# 15_FPGA_misc_banks.net
KiCad netlist of a schematic drawn in Altium Designer
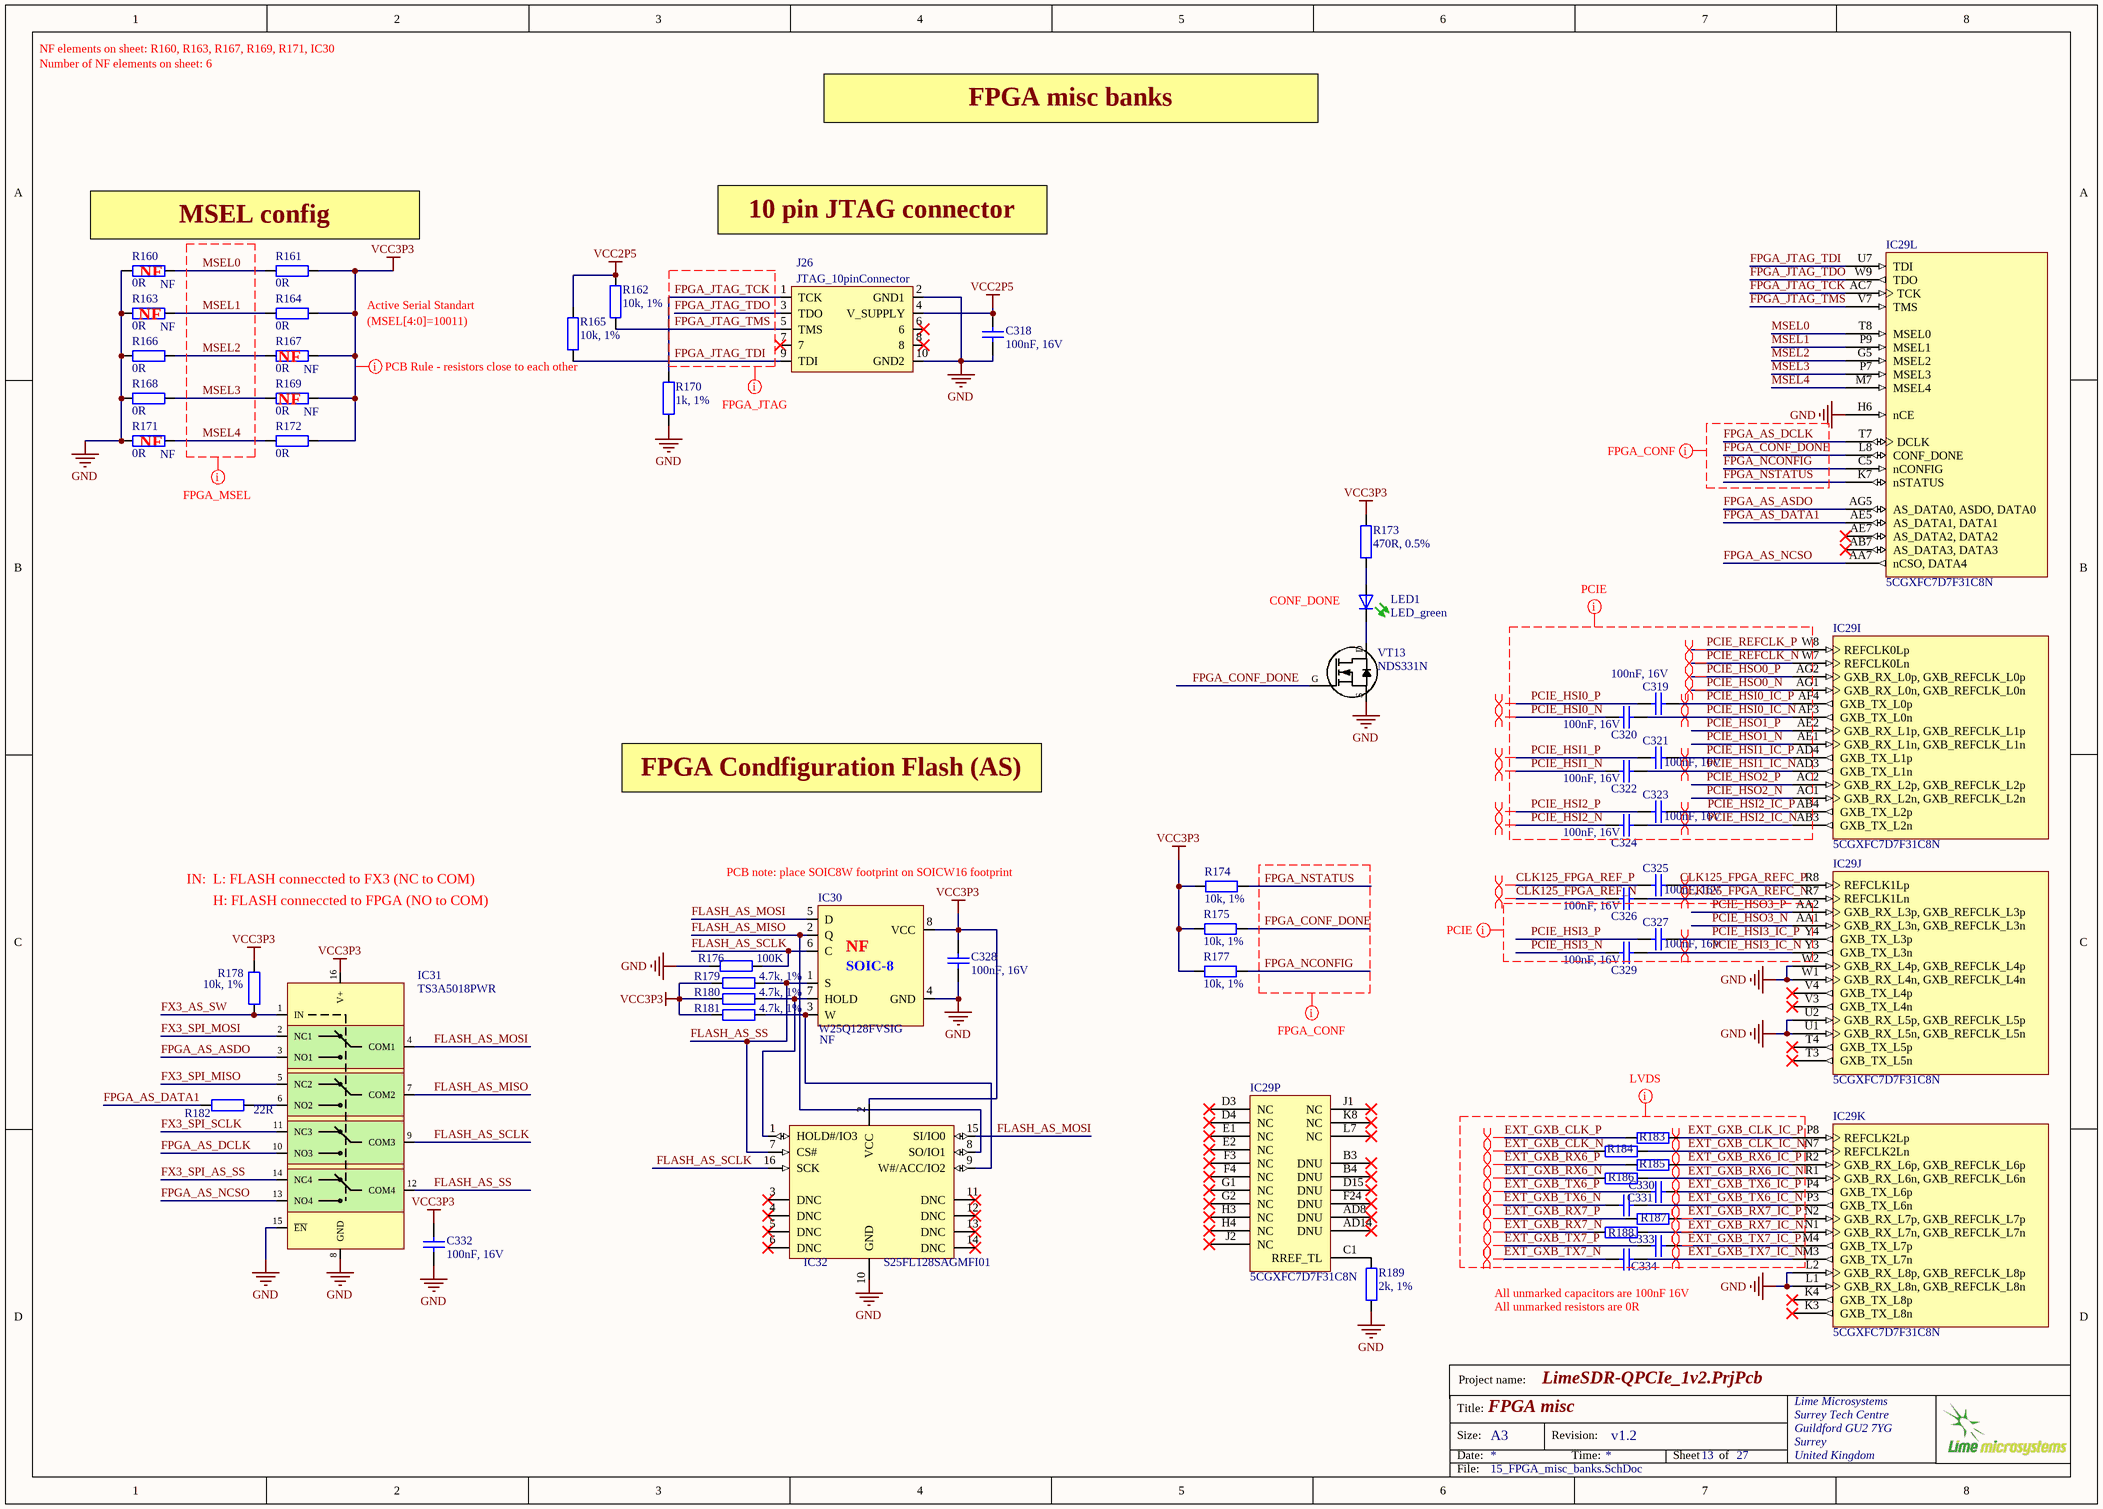
[diagram p0: 15_FPGA_misc_banks.SchDoc]

(export (version "E")
  (design (tool "Eeschema 10.0.6"))
  (components
    (comp (ref "C318")
      (value "100nF, 16V")
      (footprint "CAP0402")
      (fields
        (field (name "TOLERANCE") "10 %")
        (field (name "MANUFACTURER") "Murata Electronics")
        (field (name "MANUFACTURER PART NUMBER") "GRM155R71C104KA88D")
      )
      (libsource (lib "LimeFPGAboard_schLib") (part "Cap_0603"))
    )
    (comp (ref "C319")
      (value "100nF, 16V")
      (footprint "CAP0402")
      (fields
        (field (name "TOLERANCE") "10 %")
        (field (name "MANUFACTURER") "Murata Electronics")
        (field (name "MANUFACTURER PART NUMBER") "GRM155R71C104KA88D")
      )
      (libsource (lib "LimeFPGAboard_schLib") (part "Cap_0603"))
    )
    (comp (ref "C320")
      (value "100nF, 16V")
      (footprint "CAP0402")
      (fields
        (field (name "TOLERANCE") "10 %")
        (field (name "MANUFACTURER") "Murata Electronics")
        (field (name "MANUFACTURER PART NUMBER") "GRM155R71C104KA88D")
      )
      (libsource (lib "LimeFPGAboard_schLib") (part "Cap_0603"))
    )
    (comp (ref "C321")
      (value "100nF, 16V")
      (footprint "CAP0402")
      (fields
        (field (name "TOLERANCE") "10 %")
        (field (name "MANUFACTURER") "Murata Electronics")
        (field (name "MANUFACTURER PART NUMBER") "GRM155R71C104KA88D")
      )
      (libsource (lib "LimeFPGAboard_schLib") (part "Cap_0603"))
    )
    (comp (ref "C322")
      (value "100nF, 16V")
      (footprint "CAP0402")
      (fields
        (field (name "TOLERANCE") "10 %")
        (field (name "MANUFACTURER") "Murata Electronics")
        (field (name "MANUFACTURER PART NUMBER") "GRM155R71C104KA88D")
      )
      (libsource (lib "LimeFPGAboard_schLib") (part "Cap_0603"))
    )
    (comp (ref "C323")
      (value "100nF, 16V")
      (footprint "CAP0402")
      (fields
        (field (name "TOLERANCE") "10 %")
        (field (name "MANUFACTURER") "Murata Electronics")
        (field (name "MANUFACTURER PART NUMBER") "GRM155R71C104KA88D")
      )
      (libsource (lib "LimeFPGAboard_schLib") (part "Cap_0603"))
    )
    (comp (ref "C324")
      (value "100nF, 16V")
      (footprint "CAP0402")
      (fields
        (field (name "TOLERANCE") "10 %")
        (field (name "MANUFACTURER") "Murata Electronics")
        (field (name "MANUFACTURER PART NUMBER") "GRM155R71C104KA88D")
      )
      (libsource (lib "LimeFPGAboard_schLib") (part "Cap_0603"))
    )
    (comp (ref "C325")
      (value "100nF, 16V")
      (footprint "CAP0402")
      (fields
        (field (name "TOLERANCE") "10 %")
        (field (name "MANUFACTURER") "Murata Electronics")
        (field (name "MANUFACTURER PART NUMBER") "GRM155R71C104KA88D")
      )
      (libsource (lib "LimeFPGAboard_schLib") (part "Cap_0603"))
    )
    (comp (ref "C326")
      (value "100nF, 16V")
      (footprint "CAP0402")
      (fields
        (field (name "TOLERANCE") "10 %")
        (field (name "MANUFACTURER") "Murata Electronics")
        (field (name "MANUFACTURER PART NUMBER") "GRM155R71C104KA88D")
      )
      (libsource (lib "LimeFPGAboard_schLib") (part "Cap_0603"))
    )
    (comp (ref "C327")
      (value "100nF, 16V")
      (footprint "CAP0402")
      (fields
        (field (name "TOLERANCE") "10 %")
        (field (name "MANUFACTURER") "Murata Electronics")
        (field (name "MANUFACTURER PART NUMBER") "GRM155R71C104KA88D")
      )
      (libsource (lib "LimeFPGAboard_schLib") (part "Cap_0603"))
    )
    (comp (ref "C328")
      (value "100nF, 16V")
      (footprint "CAP0402")
      (fields
        (field (name "TOLERANCE") "10 %")
        (field (name "MANUFACTURER") "Murata Electronics")
        (field (name "MANUFACTURER PART NUMBER") "GRM155R71C104KA88D")
      )
      (libsource (lib "LimeFPGAboard_schLib") (part "Cap_0603"))
    )
    (comp (ref "C329")
      (value "100nF, 16V")
      (footprint "CAP0402")
      (fields
        (field (name "TOLERANCE") "10 %")
        (field (name "MANUFACTURER") "Murata Electronics")
        (field (name "MANUFACTURER PART NUMBER") "GRM155R71C104KA88D")
      )
      (libsource (lib "LimeFPGAboard_schLib") (part "Cap_0603"))
    )
    (comp (ref "C330")
      (value "100nF, 16V")
      (footprint "CAP0402")
      (fields
        (field (name "TOLERANCE") "10 %")
        (field (name "MANUFACTURER") "Murata Electronics")
        (field (name "MANUFACTURER PART NUMBER") "GRM155R71C104KA88D")
      )
      (libsource (lib "LimeFPGAboard_schLib") (part "Cap_0603"))
    )
    (comp (ref "C331")
      (value "100nF, 16V")
      (footprint "CAP0402")
      (fields
        (field (name "TOLERANCE") "10 %")
        (field (name "MANUFACTURER") "Murata Electronics")
        (field (name "MANUFACTURER PART NUMBER") "GRM155R71C104KA88D")
      )
      (libsource (lib "LimeFPGAboard_schLib") (part "Cap_0603"))
    )
    (comp (ref "C332")
      (value "100nF, 16V")
      (footprint "CAP0402")
      (fields
        (field (name "TOLERANCE") "10 %")
        (field (name "MANUFACTURER") "Murata Electronics")
        (field (name "MANUFACTURER PART NUMBER") "GRM155R71C104KA88D")
      )
      (libsource (lib "LimeFPGAboard_schLib") (part "Cap_0603"))
    )
    (comp (ref "C333")
      (value "100nF, 16V")
      (footprint "CAP0402")
      (fields
        (field (name "TOLERANCE") "10 %")
        (field (name "MANUFACTURER") "Murata Electronics")
        (field (name "MANUFACTURER PART NUMBER") "GRM155R71C104KA88D")
      )
      (libsource (lib "LimeFPGAboard_schLib") (part "Cap_0603"))
    )
    (comp (ref "C334")
      (value "100nF, 16V")
      (footprint "CAP0402")
      (fields
        (field (name "TOLERANCE") "10 %")
        (field (name "MANUFACTURER") "Murata Electronics")
        (field (name "MANUFACTURER PART NUMBER") "GRM155R71C104KA88D")
      )
      (libsource (lib "LimeFPGAboard_schLib") (part "Cap_0603"))
    )
    (comp (ref "IC29")
      (value "5CGXFC7D7F31C8N")
      (footprint "ALTR-FBGA896_A-200")
      (fields (field (name "MANUFACTURER") "Altera"))
      (libsource (lib "LimeMicroAltiumLib_schLib") (part "5CGXFC7D7F31C8N"))
    )
    (comp (ref "IC30")
      (value "W25Q128FVSIG")
      (footprint "S25FL164K_WSO8N")
      (fields (field (name "MANUFACTURER") "Winbond Electronics") (field (name "ASSEMBLY INFO") "NF"))
      (libsource (lib "LimeFPGAboard_schLib") (part "M25P40"))
    )
    (comp (ref "IC31")
      (value "TS3A5018PWR")
      (footprint "TS3A5018PWR")
      (fields (field (name "MANUFACTURER") "Texas Instruments"))
      (libsource (lib "LimeFPGAboard_schLib") (part "TS3A5018PWR"))
    )
    (comp (ref "IC32")
      (value "S25FL128SAGMFI01")
      (footprint "SOIC16_WIDE")
      (fields
        (field (name "MANUFACTURER PART NUMBER") "S25FL128SAGMFI010")
        (field (name "MANUFACTURER") "Spansion")
      )
      (libsource (lib "LimeMicroAltiumLib_schLib") (part "S25FL032P"))
    )
    (comp (ref "J26")
      (value "JTAG_10pinConnector")
      (footprint "HEADER5x2_SM")
      (fields (field (name "MANUFACTURER") "Amphenol FCI"))
      (libsource (lib "LimeFPGAboard_schLib") (part "JTAG_connector_10pin"))
    )
    (comp (ref "LED1")
      (value "LED_green")
      (footprint "LED-0603-GREEN")
      (fields (field (name "MANUFACTURER") "Avago Technologies US Inc."))
      (libsource (lib "LimeFPGAboard_schLib") (part "LED_green"))
    )
    (comp (ref "R160")
      (value "0R")
      (footprint "RES0402")
      (fields (field (name "MANUFACTURER") "Yageo") (field (name "ASSEMBLY INFO") "NF"))
      (libsource (lib "LimeFPGAboard_schLib") (part "Res_0402"))
    )
    (comp (ref "R161")
      (value "0R")
      (footprint "RES0402")
      (fields (field (name "MANUFACTURER") "Yageo"))
      (libsource (lib "LimeFPGAboard_schLib") (part "Res_0402"))
    )
    (comp (ref "R162")
      (value "10k, 1%")
      (footprint "RES0402")
      (fields (field (name "MANUFACTURER") "Yageo") (field (name "TOLERANCE") "±1%"))
      (libsource (lib "LimeMicroAltiumLib_schLib") (part "Res_0402"))
    )
    (comp (ref "R163")
      (value "0R")
      (footprint "RES0402")
      (fields (field (name "MANUFACTURER") "Yageo") (field (name "ASSEMBLY INFO") "NF"))
      (libsource (lib "LimeFPGAboard_schLib") (part "Res_0402"))
    )
    (comp (ref "R164")
      (value "0R")
      (footprint "RES0402")
      (fields (field (name "MANUFACTURER") "Yageo"))
      (libsource (lib "LimeFPGAboard_schLib") (part "Res_0402"))
    )
    (comp (ref "R165")
      (value "10k, 1%")
      (footprint "RES0402")
      (fields (field (name "MANUFACTURER") "Yageo") (field (name "TOLERANCE") "±1%"))
      (libsource (lib "LimeMicroAltiumLib_schLib") (part "Res_0402"))
    )
    (comp (ref "R166")
      (value "0R")
      (footprint "RES0402")
      (fields (field (name "MANUFACTURER") "Yageo"))
      (libsource (lib "LimeFPGAboard_schLib") (part "Res_0402"))
    )
    (comp (ref "R167")
      (value "0R")
      (footprint "RES0402")
      (fields (field (name "MANUFACTURER") "Yageo") (field (name "ASSEMBLY INFO") "NF"))
      (libsource (lib "LimeFPGAboard_schLib") (part "Res_0402"))
    )
    (comp (ref "R168")
      (value "0R")
      (footprint "RES0402")
      (fields (field (name "MANUFACTURER") "Yageo"))
      (libsource (lib "LimeFPGAboard_schLib") (part "Res_0402"))
    )
    (comp (ref "R169")
      (value "0R")
      (footprint "RES0402")
      (fields (field (name "MANUFACTURER") "Yageo") (field (name "ASSEMBLY INFO") "NF"))
      (libsource (lib "LimeFPGAboard_schLib") (part "Res_0402"))
    )
    (comp (ref "R170")
      (value "1k, 1%")
      (footprint "RES0402")
      (fields (field (name "MANUFACTURER") "Stackpole Electronics Inc") (field (name "TOLERANCE") "±1%"))
      (libsource (lib "LimeMicroAltiumLib_schLib") (part "Res_0402"))
    )
    (comp (ref "R171")
      (value "0R")
      (footprint "RES0402")
      (fields (field (name "MANUFACTURER") "Yageo") (field (name "ASSEMBLY INFO") "NF"))
      (libsource (lib "LimeFPGAboard_schLib") (part "Res_0402"))
    )
    (comp (ref "R172")
      (value "0R")
      (footprint "RES0402")
      (fields (field (name "MANUFACTURER") "Yageo"))
      (libsource (lib "LimeFPGAboard_schLib") (part "Res_0402"))
    )
    (comp (ref "R173")
      (value "470R, 0.5%")
      (footprint "RES0402")
      (fields
        (field (name "TOLERANCE") "±0.5%")
        (field (name "MANUFACTURER") "Panasonic Electronic Components")
      )
      (libsource (lib "LimeFPGAboard_schLib") (part "Res_0402"))
    )
    (comp (ref "R174")
      (value "10k, 1%")
      (footprint "RES0402")
      (fields (field (name "MANUFACTURER") "Yageo") (field (name "TOLERANCE") "±1%"))
      (libsource (lib "LimeMicroAltiumLib_schLib") (part "Res_0402"))
    )
    (comp (ref "R175")
      (value "10k, 1%")
      (footprint "RES0402")
      (fields (field (name "MANUFACTURER") "Yageo") (field (name "TOLERANCE") "±1%"))
      (libsource (lib "LimeMicroAltiumLib_schLib") (part "Res_0402"))
    )
    (comp (ref "R176")
      (value "100K")
      (footprint "RES0402")
      (fields
        (field (name "TOLERANCE") "±5%")
        (field (name "MANUFACTURER") "Panasonic Electronic Components")
      )
      (libsource (lib "LimeFPGAboard_schLib") (part "Res_0402"))
    )
    (comp (ref "R177")
      (value "10k, 1%")
      (footprint "RES0402")
      (fields (field (name "MANUFACTURER") "Yageo") (field (name "TOLERANCE") "±1%"))
      (libsource (lib "LimeMicroAltiumLib_schLib") (part "Res_0402"))
    )
    (comp (ref "R178")
      (value "10k, 1%")
      (footprint "RES0402")
      (fields (field (name "MANUFACTURER") "Yageo") (field (name "TOLERANCE") "±1%"))
      (libsource (lib "LimeMicroAltiumLib_schLib") (part "Res_0402"))
    )
    (comp (ref "R179")
      (value "4.7k, 1%")
      (footprint "RES0402")
      (fields (field (name "MANUFACTURER") "Yageo") (field (name "TOLERANCE") "±1%"))
      (libsource (lib "LimeMicroAltiumLib_schLib") (part "Res_0402"))
    )
    (comp (ref "R180")
      (value "4.7k, 1%")
      (footprint "RES0402")
      (fields (field (name "MANUFACTURER") "Yageo") (field (name "TOLERANCE") "±1%"))
      (libsource (lib "LimeMicroAltiumLib_schLib") (part "Res_0402"))
    )
    (comp (ref "R181")
      (value "4.7k, 1%")
      (footprint "RES0402")
      (fields (field (name "MANUFACTURER") "Yageo") (field (name "TOLERANCE") "±1%"))
      (libsource (lib "LimeMicroAltiumLib_schLib") (part "Res_0402"))
    )
    (comp (ref "R182")
      (value "22R")
      (footprint "RES0402")
      (fields (field (name "TOLERANCE") "±1%") (field (name "MANUFACTURER") "Yageo"))
      (libsource (lib "LimeFPGAboard_schLib") (part "Res_0402"))
    )
    (comp (ref "R183")
      (value "0R")
      (footprint "RES0402")
      (fields (field (name "MANUFACTURER") "Yageo") (field (name "TOLERANCE") "Jumper"))
      (libsource (lib "LimeMicroAltiumLib_schLib") (part "Res_0402"))
    )
    (comp (ref "R184")
      (value "0R")
      (footprint "RES0402")
      (fields (field (name "MANUFACTURER") "Yageo") (field (name "TOLERANCE") "Jumper"))
      (libsource (lib "LimeMicroAltiumLib_schLib") (part "Res_0402"))
    )
    (comp (ref "R185")
      (value "0R")
      (footprint "RES0402")
      (fields (field (name "MANUFACTURER") "Yageo") (field (name "TOLERANCE") "Jumper"))
      (libsource (lib "LimeMicroAltiumLib_schLib") (part "Res_0402"))
    )
    (comp (ref "R186")
      (value "0R")
      (footprint "RES0402")
      (fields (field (name "MANUFACTURER") "Yageo") (field (name "TOLERANCE") "Jumper"))
      (libsource (lib "LimeMicroAltiumLib_schLib") (part "Res_0402"))
    )
    (comp (ref "R187")
      (value "0R")
      (footprint "RES0402")
      (fields (field (name "MANUFACTURER") "Yageo") (field (name "TOLERANCE") "Jumper"))
      (libsource (lib "LimeMicroAltiumLib_schLib") (part "Res_0402"))
    )
    (comp (ref "R188")
      (value "0R")
      (footprint "RES0402")
      (fields (field (name "MANUFACTURER") "Yageo") (field (name "TOLERANCE") "Jumper"))
      (libsource (lib "LimeMicroAltiumLib_schLib") (part "Res_0402"))
    )
    (comp (ref "R189")
      (value "2k, 1%")
      (footprint "RES0402")
      (fields (field (name "MANUFACTURER") "Yageo") (field (name "TOLERANCE") "±1%"))
      (libsource (lib "LimeMicroAltiumLib_schLib") (part "Res_0402"))
    )
    (comp (ref "VT13")
      (value "NDS331N")
      (footprint "SOT23-3")
      (fields (field (name "MANUFACTURER") "Fairchild Semiconductor"))
      (libsource (lib "LimeFPGAboard_schLib") (part "NDS331N"))
    )
  )
  (nets
    (net (code "1") (name "/CLK125_FPGA_REFC_N") (class "Default")
      (node (ref "C326") (pin "1") (pinfunction "1_1") (pintype "passive"))
      (node (ref "IC29") (pin "R7") (pinfunction "REFCLK1Ln_R7") (pintype "input"))
    )
    (net (code "2") (name "/CLK125_FPGA_REFC_P") (class "Default")
      (node (ref "C325") (pin "1") (pinfunction "1_1") (pintype "passive"))
      (node (ref "IC29") (pin "R8") (pinfunction "REFCLK1Lp_R8") (pintype "input"))
    )
    (net (code "3") (name "/CLK125_FPGA_REF_N") (class "Default")
      (node (ref "C326") (pin "2") (pinfunction "2_2") (pintype "passive"))
    )
    (net (code "4") (name "/CLK125_FPGA_REF_P") (class "Default")
      (node (ref "C325") (pin "2") (pinfunction "2_2") (pintype "passive"))
    )
    (net (code "5") (name "/EXT_GXB_CLK_IC_N") (class "Default")
      (node (ref "IC29") (pin "N7") (pinfunction "REFCLK2Ln_N7") (pintype "input"))
      (node (ref "R184") (pin "1") (pinfunction "1_1") (pintype "passive"))
    )
    (net (code "6") (name "/EXT_GXB_CLK_IC_P") (class "Default")
      (node (ref "IC29") (pin "P8") (pinfunction "REFCLK2Lp_P8") (pintype "input"))
      (node (ref "R183") (pin "1") (pinfunction "1_1") (pintype "passive"))
    )
    (net (code "7") (name "/EXT_GXB_CLK_N") (class "Default")
      (node (ref "R184") (pin "2") (pinfunction "2_2") (pintype "passive"))
    )
    (net (code "8") (name "/EXT_GXB_CLK_P") (class "Default")
      (node (ref "R183") (pin "2") (pinfunction "2_2") (pintype "passive"))
    )
    (net (code "10") (name "/EXT_GXB_RX6_IC_N") (class "Default")
      (node (ref "IC29") (pin "R1") (pinfunction "GXB_RX_L6n,_GXB_REFCLK_L6n_R1") (pintype "input"))
      (node (ref "R186") (pin "1") (pinfunction "1_1") (pintype "passive"))
    )
    (net (code "11") (name "/EXT_GXB_RX6_IC_P") (class "Default")
      (node (ref "IC29") (pin "R2") (pinfunction "GXB_RX_L6p,_GXB_REFCLK_L6p_R2") (pintype "input"))
      (node (ref "R185") (pin "1") (pinfunction "1_1") (pintype "passive"))
    )
    (net (code "12") (name "/EXT_GXB_RX6_N") (class "Default")
      (node (ref "R186") (pin "2") (pinfunction "2_2") (pintype "passive"))
    )
    (net (code "14") (name "/EXT_GXB_RX6_P") (class "Default")
      (node (ref "R185") (pin "2") (pinfunction "2_2") (pintype "passive"))
    )
    (net (code "15") (name "/EXT_GXB_RX7_IC_N") (class "Default")
      (node (ref "IC29") (pin "N1") (pinfunction "GXB_RX_L7n,_GXB_REFCLK_L7n_N1") (pintype "input"))
      (node (ref "R188") (pin "1") (pinfunction "1_1") (pintype "passive"))
    )
    (net (code "16") (name "/EXT_GXB_RX7_IC_P") (class "Default")
      (node (ref "IC29") (pin "N2") (pinfunction "GXB_RX_L7p,_GXB_REFCLK_L7p_N2") (pintype "input"))
      (node (ref "R187") (pin "1") (pinfunction "1_1") (pintype "passive"))
    )
    (net (code "17") (name "/EXT_GXB_RX7_N") (class "Default")
      (node (ref "R188") (pin "2") (pinfunction "2_2") (pintype "passive"))
    )
    (net (code "18") (name "/EXT_GXB_RX7_P") (class "Default")
      (node (ref "R187") (pin "2") (pinfunction "2_2") (pintype "passive"))
    )
    (net (code "19") (name "/EXT_GXB_TX6_IC_N") (class "Default")
      (node (ref "C331") (pin "1") (pinfunction "1_1") (pintype "passive"))
      (node (ref "IC29") (pin "P3") (pinfunction "GXB_TX_L6n_P3") (pintype "output"))
    )
    (net (code "20") (name "/EXT_GXB_TX6_IC_P") (class "Default")
      (node (ref "C330") (pin "1") (pinfunction "1_1") (pintype "passive"))
      (node (ref "IC29") (pin "P4") (pinfunction "GXB_TX_L6p_P4") (pintype "output"))
    )
    (net (code "21") (name "/EXT_GXB_TX6_N") (class "Default")
      (node (ref "C331") (pin "2") (pinfunction "2_2") (pintype "passive"))
    )
    (net (code "23") (name "/EXT_GXB_TX6_P") (class "Default")
      (node (ref "C330") (pin "2") (pinfunction "2_2") (pintype "passive"))
    )
    (net (code "24") (name "/EXT_GXB_TX7_IC_N") (class "Default")
      (node (ref "C334") (pin "1") (pinfunction "1_1") (pintype "passive"))
      (node (ref "IC29") (pin "M3") (pinfunction "GXB_TX_L7n_M3") (pintype "output"))
    )
    (net (code "25") (name "/EXT_GXB_TX7_IC_P") (class "Default")
      (node (ref "C333") (pin "1") (pinfunction "1_1") (pintype "passive"))
      (node (ref "IC29") (pin "M4") (pinfunction "GXB_TX_L7p_M4") (pintype "output"))
    )
    (net (code "26") (name "/EXT_GXB_TX7_N") (class "Default")
      (node (ref "C334") (pin "2") (pinfunction "2_2") (pintype "passive"))
    )
    (net (code "27") (name "/EXT_GXB_TX7_P") (class "Default")
      (node (ref "C333") (pin "2") (pinfunction "2_2") (pintype "passive"))
    )
    (net (code "28") (name "/FLASH_AS_MISO") (class "Default")
      (node (ref "IC30") (pin "2") (pinfunction "Q_2") (pintype "passive"))
      (node (ref "IC31") (pin "7") (pinfunction "COM2_7") (pintype "passive"))
      (node (ref "IC32") (pin "8") (pinfunction "SO/IO1_8") (pintype "bidirectional"))
    )
    (net (code "29") (name "/FLASH_AS_MOSI") (class "Default")
      (node (ref "IC30") (pin "5") (pinfunction "D_5") (pintype "passive"))
      (node (ref "IC31") (pin "4") (pinfunction "COM1_4") (pintype "passive"))
      (node (ref "IC32") (pin "15") (pinfunction "SI/IO0_15") (pintype "bidirectional"))
    )
    (net (code "30") (name "/FLASH_AS_SCLK") (class "Default")
      (node (ref "IC30") (pin "6") (pinfunction "C_6") (pintype "passive"))
      (node (ref "IC31") (pin "9") (pinfunction "COM3_9") (pintype "passive"))
      (node (ref "IC32") (pin "16") (pinfunction "SCK_16") (pintype "input"))
      (node (ref "R176") (pin "1") (pinfunction "1_1") (pintype "passive"))
    )
    (net (code "31") (name "/FLASH_AS_SS") (class "Default")
      (node (ref "IC30") (pin "1") (pinfunction "S_1") (pintype "passive"))
      (node (ref "IC31") (pin "12") (pinfunction "COM4_12") (pintype "passive"))
      (node (ref "IC32") (pin "7") (pinfunction "CS#_7") (pintype "input"))
      (node (ref "R179") (pin "1") (pinfunction "1_1") (pintype "passive"))
    )
    (net (code "32") (name "/FPGA_AS_ASDO") (class "Default")
      (node (ref "IC29") (pin "AG5") (pinfunction "AS_DATA0,_ASDO,_DATA0_AG5") (pintype "bidirectional"))
      (node (ref "IC31") (pin "3") (pinfunction "NO1_3") (pintype "passive"))
    )
    (net (code "33") (name "/FPGA_AS_DATA1") (class "Default")
      (node (ref "IC29") (pin "AE5") (pinfunction "AS_DATA1,_DATA1_AE5") (pintype "bidirectional"))
      (node (ref "R182") (pin "2") (pinfunction "2_2") (pintype "passive"))
    )
    (net (code "34") (name "/FPGA_AS_DCLK") (class "Default")
      (node (ref "IC29") (pin "T7") (pinfunction "DCLK_T7") (pintype "bidirectional"))
      (node (ref "IC31") (pin "10") (pinfunction "NO3_10") (pintype "passive"))
    )
    (net (code "35") (name "/FPGA_AS_NCSO") (class "Default")
      (node (ref "IC29") (pin "AA7") (pinfunction "nCSO,_DATA4_AA7") (pintype "output"))
      (node (ref "IC31") (pin "13") (pinfunction "NO4_13") (pintype "passive"))
    )
    (net (code "36") (name "/FPGA_CONF_DONE") (class "Default")
      (node (ref "IC29") (pin "L8") (pinfunction "CONF_DONE_L8") (pintype "bidirectional"))
      (node (ref "R175") (pin "2") (pinfunction "2_2") (pintype "passive"))
      (node (ref "VT13") (pin "G") (pinfunction "G_G") (pintype "passive"))
    )
    (net (code "37") (name "/FPGA_JTAG_TCK") (class "Default")
      (node (ref "IC29") (pin "AC7") (pinfunction "TCK_AC7") (pintype "input"))
      (node (ref "J26") (pin "1") (pinfunction "TCK_1") (pintype "passive"))
      (node (ref "R170") (pin "1") (pinfunction "1_1") (pintype "passive"))
    )
    (net (code "38") (name "/FPGA_JTAG_TDI") (class "Default")
      (node (ref "IC29") (pin "U7") (pinfunction "TDI_U7") (pintype "input"))
      (node (ref "J26") (pin "9") (pinfunction "TDI_9") (pintype "passive"))
      (node (ref "R165") (pin "2") (pinfunction "2_2") (pintype "passive"))
    )
    (net (code "39") (name "/FPGA_JTAG_TDO") (class "Default")
      (node (ref "IC29") (pin "W9") (pinfunction "TDO_W9") (pintype "output"))
      (node (ref "J26") (pin "3") (pinfunction "TDO_3") (pintype "passive"))
    )
    (net (code "40") (name "/FPGA_JTAG_TMS") (class "Default")
      (node (ref "IC29") (pin "V7") (pinfunction "TMS_V7") (pintype "input"))
      (node (ref "J26") (pin "5") (pinfunction "TMS_5") (pintype "passive"))
      (node (ref "R162") (pin "2") (pinfunction "2_2") (pintype "passive"))
    )
    (net (code "41") (name "/FPGA_NCONFIG") (class "Default")
      (node (ref "IC29") (pin "C5") (pinfunction "nCONFIG_C5") (pintype "input"))
      (node (ref "R177") (pin "2") (pinfunction "2_2") (pintype "passive"))
    )
    (net (code "42") (name "/FPGA_NSTATUS") (class "Default")
      (node (ref "IC29") (pin "K7") (pinfunction "nSTATUS_K7") (pintype "bidirectional"))
      (node (ref "R174") (pin "2") (pinfunction "2_2") (pintype "passive"))
    )
    (net (code "43") (name "/FX3_AS_SW") (class "Default")
      (node (ref "IC31") (pin "1") (pinfunction "IN_1") (pintype "passive"))
      (node (ref "R178") (pin "1") (pinfunction "1_1") (pintype "passive"))
    )
    (net (code "44") (name "/FX3_SPI_AS_SS") (class "Default")
      (node (ref "IC31") (pin "14") (pinfunction "NC4_14") (pintype "passive"))
    )
    (net (code "45") (name "/FX3_SPI_MISO") (class "Default")
      (node (ref "IC31") (pin "5") (pinfunction "NC2_5") (pintype "passive"))
    )
    (net (code "46") (name "/FX3_SPI_MOSI") (class "Default")
      (node (ref "IC31") (pin "2") (pinfunction "NC1_2") (pintype "passive"))
    )
    (net (code "47") (name "/FX3_SPI_SCLK") (class "Default")
      (node (ref "IC31") (pin "11") (pinfunction "NC3_11") (pintype "passive"))
    )
    (net (code "48") (name "/MSEL0") (class "Default")
      (node (ref "IC29") (pin "T8") (pinfunction "MSEL0_T8") (pintype "input"))
      (node (ref "R160") (pin "1") (pinfunction "1_1") (pintype "passive"))
      (node (ref "R161") (pin "2") (pinfunction "2_2") (pintype "passive"))
    )
    (net (code "49") (name "/MSEL1") (class "Default")
      (node (ref "IC29") (pin "P9") (pinfunction "MSEL1_P9") (pintype "input"))
      (node (ref "R163") (pin "1") (pinfunction "1_1") (pintype "passive"))
      (node (ref "R164") (pin "2") (pinfunction "2_2") (pintype "passive"))
    )
    (net (code "50") (name "/MSEL2") (class "Default")
      (node (ref "IC29") (pin "G5") (pinfunction "MSEL2_G5") (pintype "input"))
      (node (ref "R166") (pin "1") (pinfunction "1_1") (pintype "passive"))
      (node (ref "R167") (pin "2") (pinfunction "2_2") (pintype "passive"))
    )
    (net (code "51") (name "/MSEL3") (class "Default")
      (node (ref "IC29") (pin "P7") (pinfunction "MSEL3_P7") (pintype "input"))
      (node (ref "R168") (pin "1") (pinfunction "1_1") (pintype "passive"))
      (node (ref "R169") (pin "2") (pinfunction "2_2") (pintype "passive"))
    )
    (net (code "52") (name "/MSEL4") (class "Default")
      (node (ref "IC29") (pin "M7") (pinfunction "MSEL4_M7") (pintype "input"))
      (node (ref "R171") (pin "1") (pinfunction "1_1") (pintype "passive"))
      (node (ref "R172") (pin "2") (pinfunction "2_2") (pintype "passive"))
    )
    (net (code "53") (name "/PCIE_HSI0_IC_N") (class "Default")
      (node (ref "C320") (pin "1") (pinfunction "1_1") (pintype "passive"))
      (node (ref "IC29") (pin "AF3") (pinfunction "GXB_TX_L0n_AF3") (pintype "output"))
    )
    (net (code "54") (name "/PCIE_HSI0_IC_P") (class "Default")
      (node (ref "C319") (pin "1") (pinfunction "1_1") (pintype "passive"))
      (node (ref "IC29") (pin "AF4") (pinfunction "GXB_TX_L0p_AF4") (pintype "output"))
    )
    (net (code "55") (name "/PCIE_HSI0_N") (class "Default")
      (node (ref "C320") (pin "2") (pinfunction "2_2") (pintype "passive"))
    )
    (net (code "56") (name "/PCIE_HSI0_P") (class "Default")
      (node (ref "C319") (pin "2") (pinfunction "2_2") (pintype "passive"))
    )
    (net (code "57") (name "/PCIE_HSI1_IC_N") (class "Default")
      (node (ref "C322") (pin "1") (pinfunction "1_1") (pintype "passive"))
      (node (ref "IC29") (pin "AD3") (pinfunction "GXB_TX_L1n_AD3") (pintype "output"))
    )
    (net (code "58") (name "/PCIE_HSI1_IC_P") (class "Default")
      (node (ref "C321") (pin "1") (pinfunction "1_1") (pintype "passive"))
      (node (ref "IC29") (pin "AD4") (pinfunction "GXB_TX_L1p_AD4") (pintype "output"))
    )
    (net (code "59") (name "/PCIE_HSI1_N") (class "Default")
      (node (ref "C322") (pin "2") (pinfunction "2_2") (pintype "passive"))
    )
    (net (code "60") (name "/PCIE_HSI1_P") (class "Default")
      (node (ref "C321") (pin "2") (pinfunction "2_2") (pintype "passive"))
    )
    (net (code "61") (name "/PCIE_HSI2_IC_N") (class "Default")
      (node (ref "C324") (pin "1") (pinfunction "1_1") (pintype "passive"))
      (node (ref "IC29") (pin "AB3") (pinfunction "GXB_TX_L2n_AB3") (pintype "output"))
    )
    (net (code "62") (name "/PCIE_HSI2_IC_P") (class "Default")
      (node (ref "C323") (pin "1") (pinfunction "1_1") (pintype "passive"))
      (node (ref "IC29") (pin "AB4") (pinfunction "GXB_TX_L2p_AB4") (pintype "output"))
    )
    (net (code "63") (name "/PCIE_HSI2_N") (class "Default")
      (node (ref "C324") (pin "2") (pinfunction "2_2") (pintype "passive"))
    )
    (net (code "64") (name "/PCIE_HSI2_P") (class "Default")
      (node (ref "C323") (pin "2") (pinfunction "2_2") (pintype "passive"))
    )
    (net (code "65") (name "/PCIE_HSI3_IC_N") (class "Default")
      (node (ref "C329") (pin "1") (pinfunction "1_1") (pintype "passive"))
      (node (ref "IC29") (pin "Y3") (pinfunction "GXB_TX_L3n_Y3") (pintype "output"))
    )
    (net (code "66") (name "/PCIE_HSI3_IC_P") (class "Default")
      (node (ref "C327") (pin "1") (pinfunction "1_1") (pintype "passive"))
      (node (ref "IC29") (pin "Y4") (pinfunction "GXB_TX_L3p_Y4") (pintype "output"))
    )
    (net (code "67") (name "/PCIE_HSI3_N") (class "Default")
      (node (ref "C329") (pin "2") (pinfunction "2_2") (pintype "passive"))
    )
    (net (code "68") (name "/PCIE_HSI3_P") (class "Default")
      (node (ref "C327") (pin "2") (pinfunction "2_2") (pintype "passive"))
    )
    (net (code "69") (name "/PCIE_HSO0_N") (class "Default")
      (node (ref "IC29") (pin "AG1") (pinfunction "GXB_RX_L0n,_GXB_REFCLK_L0n_AG1") (pintype "input"))
    )
    (net (code "70") (name "/PCIE_HSO0_P") (class "Default")
      (node (ref "IC29") (pin "AG2") (pinfunction "GXB_RX_L0p,_GXB_REFCLK_L0p_AG2") (pintype "input"))
    )
    (net (code "71") (name "/PCIE_HSO1_N") (class "Default")
      (node (ref "IC29") (pin "AE1") (pinfunction "GXB_RX_L1n,_GXB_REFCLK_L1n_AE1") (pintype "input"))
    )
    (net (code "72") (name "/PCIE_HSO1_P") (class "Default")
      (node (ref "IC29") (pin "AE2") (pinfunction "GXB_RX_L1p,_GXB_REFCLK_L1p_AE2") (pintype "input"))
    )
    (net (code "73") (name "/PCIE_HSO2_N") (class "Default")
      (node (ref "IC29") (pin "AC1") (pinfunction "GXB_RX_L2n,_GXB_REFCLK_L2n_AC1") (pintype "input"))
    )
    (net (code "74") (name "/PCIE_HSO2_P") (class "Default")
      (node (ref "IC29") (pin "AC2") (pinfunction "GXB_RX_L2p,_GXB_REFCLK_L2p_AC2") (pintype "input"))
    )
    (net (code "75") (name "/PCIE_HSO3_N") (class "Default")
      (node (ref "IC29") (pin "AA1") (pinfunction "GXB_RX_L3n,_GXB_REFCLK_L3n_AA1") (pintype "input"))
    )
    (net (code "76") (name "/PCIE_HSO3_P") (class "Default")
      (node (ref "IC29") (pin "AA2") (pinfunction "GXB_RX_L3p,_GXB_REFCLK_L3p_AA2") (pintype "input"))
    )
    (net (code "77") (name "/PCIE_REFCLK_N") (class "Default")
      (node (ref "IC29") (pin "W7") (pinfunction "REFCLK0Ln_W7") (pintype "input"))
    )
    (net (code "78") (name "/PCIE_REFCLK_P") (class "Default")
      (node (ref "IC29") (pin "W8") (pinfunction "REFCLK0Lp_W8") (pintype "input"))
    )
    (net (code "79") (name "GND") (class "Default")
      (node (ref "C318") (pin "2") (pinfunction "2_2") (pintype "passive"))
      (node (ref "C328") (pin "2") (pinfunction "2_2") (pintype "passive"))
      (node (ref "C332") (pin "2") (pinfunction "2_2") (pintype "passive"))
      (node (ref "IC29") (pin "H6") (pinfunction "nCE_H6") (pintype "input"))
      (node (ref "IC29") (pin "L1") (pinfunction "GXB_RX_L8n,_GXB_REFCLK_L8n_L1") (pintype "input"))
      (node (ref "IC29") (pin "L2") (pinfunction "GXB_RX_L8p,_GXB_REFCLK_L8p_L2") (pintype "input"))
      (node (ref "IC29") (pin "U1") (pinfunction "GXB_RX_L5n,_GXB_REFCLK_L5n_U1") (pintype "input"))
      (node (ref "IC29") (pin "U2") (pinfunction "GXB_RX_L5p,_GXB_REFCLK_L5p_U2") (pintype "input"))
      (node (ref "IC29") (pin "W1") (pinfunction "GXB_RX_L4n,_GXB_REFCLK_L4n_W1") (pintype "input"))
      (node (ref "IC29") (pin "W2") (pinfunction "GXB_RX_L4p,_GXB_REFCLK_L4p_W2") (pintype "input"))
      (node (ref "IC30") (pin "4") (pinfunction "GND_4") (pintype "passive"))
      (node (ref "IC31") (pin "15") (pinfunction "~{EN}_15") (pintype "passive"))
      (node (ref "IC31") (pin "8") (pinfunction "GND_8") (pintype "passive"))
      (node (ref "IC32") (pin "10") (pinfunction "GND_10") (pintype "passive"))
      (node (ref "J26") (pin "10") (pinfunction "GND2_10") (pintype "power_in"))
      (node (ref "J26") (pin "2") (pinfunction "GND1_2") (pintype "power_in"))
      (node (ref "R160") (pin "2") (pinfunction "2_2") (pintype "passive"))
      (node (ref "R163") (pin "2") (pinfunction "2_2") (pintype "passive"))
      (node (ref "R166") (pin "2") (pinfunction "2_2") (pintype "passive"))
      (node (ref "R168") (pin "2") (pinfunction "2_2") (pintype "passive"))
      (node (ref "R170") (pin "2") (pinfunction "2_2") (pintype "passive"))
      (node (ref "R171") (pin "2") (pinfunction "2_2") (pintype "passive"))
      (node (ref "R176") (pin "2") (pinfunction "2_2") (pintype "passive"))
      (node (ref "R189") (pin "2") (pinfunction "2_2") (pintype "passive"))
      (node (ref "VT13") (pin "S") (pinfunction "S_S") (pintype "passive"))
    )
    (net (code "80") (name "Net-(IC29P-RREF_TL)") (class "Default")
      (node (ref "IC29") (pin "C1") (pinfunction "RREF_TL_C1") (pintype "passive"))
      (node (ref "R189") (pin "1") (pinfunction "1_1") (pintype "passive"))
    )
    (net (code "81") (name "Net-(IC30-HOLD)") (class "Default")
      (node (ref "IC30") (pin "7") (pinfunction "HOLD_7") (pintype "passive"))
      (node (ref "IC32") (pin "1") (pinfunction "HOLD#/IO3_1") (pintype "bidirectional"))
      (node (ref "R180") (pin "1") (pinfunction "1_1") (pintype "passive"))
    )
    (net (code "82") (name "Net-(IC30-W)") (class "Default")
      (node (ref "IC30") (pin "3") (pinfunction "W_3") (pintype "passive"))
      (node (ref "IC32") (pin "9") (pinfunction "W#/ACC/IO2_9") (pintype "bidirectional"))
      (node (ref "R181") (pin "1") (pinfunction "1_1") (pintype "passive"))
    )
    (net (code "83") (name "Net-(IC31-NO2)") (class "Default")
      (node (ref "IC31") (pin "6") (pinfunction "NO2_6") (pintype "passive"))
      (node (ref "R182") (pin "1") (pinfunction "1_1") (pintype "passive"))
    )
    (net (code "84") (name "Net-(LED1-C)") (class "Default")
      (node (ref "LED1") (pin "K") (pinfunction "C_K") (pintype "power_in"))
      (node (ref "VT13") (pin "D") (pinfunction "D_D") (pintype "passive"))
    )
    (net (code "85") (name "Net-(LED1-PadA)") (class "Default")
      (node (ref "LED1") (pin "A") (pinfunction "A_A") (pintype "power_in"))
      (node (ref "R173") (pin "1") (pinfunction "1_1") (pintype "passive"))
    )
    (net (code "86") (name "VCC2P5") (class "Default")
      (node (ref "C318") (pin "1") (pinfunction "1_1") (pintype "passive"))
      (node (ref "J26") (pin "4") (pinfunction "V_SUPPLY_4") (pintype "power_in"))
      (node (ref "R162") (pin "1") (pinfunction "1_1") (pintype "passive"))
      (node (ref "R165") (pin "1") (pinfunction "1_1") (pintype "passive"))
    )
    (net (code "87") (name "VCC3P3") (class "Default")
      (node (ref "C328") (pin "1") (pinfunction "1_1") (pintype "passive"))
      (node (ref "C332") (pin "1") (pinfunction "1_1") (pintype "passive"))
      (node (ref "IC30") (pin "8") (pinfunction "VCC_8") (pintype "passive"))
      (node (ref "IC31") (pin "16") (pinfunction "V+_16") (pintype "passive"))
      (node (ref "IC32") (pin "2") (pinfunction "VCC_2") (pintype "power_in"))
      (node (ref "R161") (pin "1") (pinfunction "1_1") (pintype "passive"))
      (node (ref "R164") (pin "1") (pinfunction "1_1") (pintype "passive"))
      (node (ref "R167") (pin "1") (pinfunction "1_1") (pintype "passive"))
      (node (ref "R169") (pin "1") (pinfunction "1_1") (pintype "passive"))
      (node (ref "R172") (pin "1") (pinfunction "1_1") (pintype "passive"))
      (node (ref "R173") (pin "2") (pinfunction "2_2") (pintype "passive"))
      (node (ref "R174") (pin "1") (pinfunction "1_1") (pintype "passive"))
      (node (ref "R175") (pin "1") (pinfunction "1_1") (pintype "passive"))
      (node (ref "R177") (pin "1") (pinfunction "1_1") (pintype "passive"))
      (node (ref "R178") (pin "2") (pinfunction "2_2") (pintype "passive"))
      (node (ref "R179") (pin "2") (pinfunction "2_2") (pintype "passive"))
      (node (ref "R180") (pin "2") (pinfunction "2_2") (pintype "passive"))
      (node (ref "R181") (pin "2") (pinfunction "2_2") (pintype "passive"))
    )
    (net (code "88") (name "unconnected-(IC29J-GXB_TX_L4n-PadV3)") (class "Default")
      (node (ref "IC29") (pin "V3") (pinfunction "GXB_TX_L4n_V3") (pintype "output+no_connect"))
    )
    (net (code "89") (name "unconnected-(IC29J-GXB_TX_L4p-PadV4)") (class "Default")
      (node (ref "IC29") (pin "V4") (pinfunction "GXB_TX_L4p_V4") (pintype "output+no_connect"))
    )
    (net (code "90") (name "unconnected-(IC29J-GXB_TX_L5n-PadT3)") (class "Default")
      (node (ref "IC29") (pin "T3") (pinfunction "GXB_TX_L5n_T3") (pintype "output+no_connect"))
    )
    (net (code "91") (name "unconnected-(IC29J-GXB_TX_L5p-PadT4)") (class "Default")
      (node (ref "IC29") (pin "T4") (pinfunction "GXB_TX_L5p_T4") (pintype "output+no_connect"))
    )
    (net (code "92") (name "unconnected-(IC29K-GXB_TX_L8n-PadK3)") (class "Default")
      (node (ref "IC29") (pin "K3") (pinfunction "GXB_TX_L8n_K3") (pintype "output+no_connect"))
    )
    (net (code "93") (name "unconnected-(IC29K-GXB_TX_L8p-PadK4)") (class "Default")
      (node (ref "IC29") (pin "K4") (pinfunction "GXB_TX_L8p_K4") (pintype "output+no_connect"))
    )
    (net (code "94") (name "unconnected-(IC29L-AS_DATA2,_DATA2-PadAE7)") (class "Default")
      (node (ref "IC29") (pin "AE7") (pinfunction "AS_DATA2,_DATA2_AE7") (pintype "bidirectional+no_connect"))
    )
    (net (code "95") (name "unconnected-(IC29L-AS_DATA3,_DATA3-PadAB7)") (class "Default")
      (node (ref "IC29") (pin "AB7") (pinfunction "AS_DATA3,_DATA3_AB7") (pintype "bidirectional+no_connect"))
    )
    (net (code "96") (name "unconnected-(IC29P-DNU-PadAD8)") (class "Default")
      (node (ref "IC29") (pin "AD8") (pinfunction "DNU_AD8") (pintype "passive+no_connect"))
    )
    (net (code "97") (name "unconnected-(IC29P-DNU-PadAD14)") (class "Default")
      (node (ref "IC29") (pin "AD14") (pinfunction "DNU_AD14") (pintype "passive+no_connect"))
    )
    (net (code "98") (name "unconnected-(IC29P-DNU-PadB3)") (class "Default")
      (node (ref "IC29") (pin "B3") (pinfunction "DNU_B3") (pintype "passive+no_connect"))
    )
    (net (code "99") (name "unconnected-(IC29P-DNU-PadB4)") (class "Default")
      (node (ref "IC29") (pin "B4") (pinfunction "DNU_B4") (pintype "passive+no_connect"))
    )
    (net (code "100") (name "unconnected-(IC29P-DNU-PadD15)") (class "Default")
      (node (ref "IC29") (pin "D15") (pinfunction "DNU_D15") (pintype "passive+no_connect"))
    )
    (net (code "101") (name "unconnected-(IC29P-DNU-PadF24)") (class "Default")
      (node (ref "IC29") (pin "F24") (pinfunction "DNU_F24") (pintype "passive+no_connect"))
    )
    (net (code "102") (name "unconnected-(IC29P-NC-PadD3)") (class "Default")
      (node (ref "IC29") (pin "D3") (pinfunction "NC_D3") (pintype "passive+no_connect"))
    )
    (net (code "103") (name "unconnected-(IC29P-NC-PadD4)") (class "Default")
      (node (ref "IC29") (pin "D4") (pinfunction "NC_D4") (pintype "passive+no_connect"))
    )
    (net (code "104") (name "unconnected-(IC29P-NC-PadE1)") (class "Default")
      (node (ref "IC29") (pin "E1") (pinfunction "NC_E1") (pintype "passive+no_connect"))
    )
    (net (code "105") (name "unconnected-(IC29P-NC-PadE2)") (class "Default")
      (node (ref "IC29") (pin "E2") (pinfunction "NC_E2") (pintype "passive+no_connect"))
    )
    (net (code "106") (name "unconnected-(IC29P-NC-PadF3)") (class "Default")
      (node (ref "IC29") (pin "F3") (pinfunction "NC_F3") (pintype "passive+no_connect"))
    )
    (net (code "107") (name "unconnected-(IC29P-NC-PadF4)") (class "Default")
      (node (ref "IC29") (pin "F4") (pinfunction "NC_F4") (pintype "passive+no_connect"))
    )
    (net (code "108") (name "unconnected-(IC29P-NC-PadG1)") (class "Default")
      (node (ref "IC29") (pin "G1") (pinfunction "NC_G1") (pintype "passive+no_connect"))
    )
    (net (code "109") (name "unconnected-(IC29P-NC-PadG2)") (class "Default")
      (node (ref "IC29") (pin "G2") (pinfunction "NC_G2") (pintype "passive+no_connect"))
    )
    (net (code "110") (name "unconnected-(IC29P-NC-PadH3)") (class "Default")
      (node (ref "IC29") (pin "H3") (pinfunction "NC_H3") (pintype "passive+no_connect"))
    )
    (net (code "111") (name "unconnected-(IC29P-NC-PadH4)") (class "Default")
      (node (ref "IC29") (pin "H4") (pinfunction "NC_H4") (pintype "passive+no_connect"))
    )
    (net (code "112") (name "unconnected-(IC29P-NC-PadJ1)") (class "Default")
      (node (ref "IC29") (pin "J1") (pinfunction "NC_J1") (pintype "passive+no_connect"))
    )
    (net (code "113") (name "unconnected-(IC29P-NC-PadJ2)") (class "Default")
      (node (ref "IC29") (pin "J2") (pinfunction "NC_J2") (pintype "passive+no_connect"))
    )
    (net (code "114") (name "unconnected-(IC29P-NC-PadK8)") (class "Default")
      (node (ref "IC29") (pin "K8") (pinfunction "NC_K8") (pintype "passive+no_connect"))
    )
    (net (code "115") (name "unconnected-(IC29P-NC-PadL7)") (class "Default")
      (node (ref "IC29") (pin "L7") (pinfunction "NC_L7") (pintype "passive+no_connect"))
    )
    (net (code "116") (name "unconnected-(IC32-DNC-Pad3)") (class "Default")
      (node (ref "IC32") (pin "3") (pinfunction "DNC_3") (pintype "passive+no_connect"))
    )
    (net (code "117") (name "unconnected-(IC32-DNC-Pad4)") (class "Default")
      (node (ref "IC32") (pin "4") (pinfunction "DNC_4") (pintype "passive+no_connect"))
    )
    (net (code "118") (name "unconnected-(IC32-DNC-Pad5)") (class "Default")
      (node (ref "IC32") (pin "5") (pinfunction "DNC_5") (pintype "passive+no_connect"))
    )
    (net (code "119") (name "unconnected-(IC32-DNC-Pad6)") (class "Default")
      (node (ref "IC32") (pin "6") (pinfunction "DNC_6") (pintype "passive+no_connect"))
    )
    (net (code "120") (name "unconnected-(IC32-DNC-Pad11)") (class "Default")
      (node (ref "IC32") (pin "11") (pinfunction "DNC_11") (pintype "passive+no_connect"))
    )
    (net (code "121") (name "unconnected-(IC32-DNC-Pad12)") (class "Default")
      (node (ref "IC32") (pin "12") (pinfunction "DNC_12") (pintype "passive+no_connect"))
    )
    (net (code "122") (name "unconnected-(IC32-DNC-Pad13)") (class "Default")
      (node (ref "IC32") (pin "13") (pinfunction "DNC_13") (pintype "passive+no_connect"))
    )
    (net (code "123") (name "unconnected-(IC32-DNC-Pad14)") (class "Default")
      (node (ref "IC32") (pin "14") (pinfunction "DNC_14") (pintype "passive+no_connect"))
    )
    (net (code "124") (name "unconnected-(J26-Pad6)") (class "Default")
      (node (ref "J26") (pin "6") (pinfunction "6_6") (pintype "passive+no_connect"))
    )
    (net (code "125") (name "unconnected-(J26-Pad7)") (class "Default")
      (node (ref "J26") (pin "7") (pinfunction "7_7") (pintype "passive+no_connect"))
    )
    (net (code "126") (name "unconnected-(J26-Pad8)") (class "Default")
      (node (ref "J26") (pin "8") (pinfunction "8_8") (pintype "passive+no_connect"))
    )
  )
)
